# BTL_IOT_STM32.net
KiCad netlist of a schematic drawn in Altium Designer
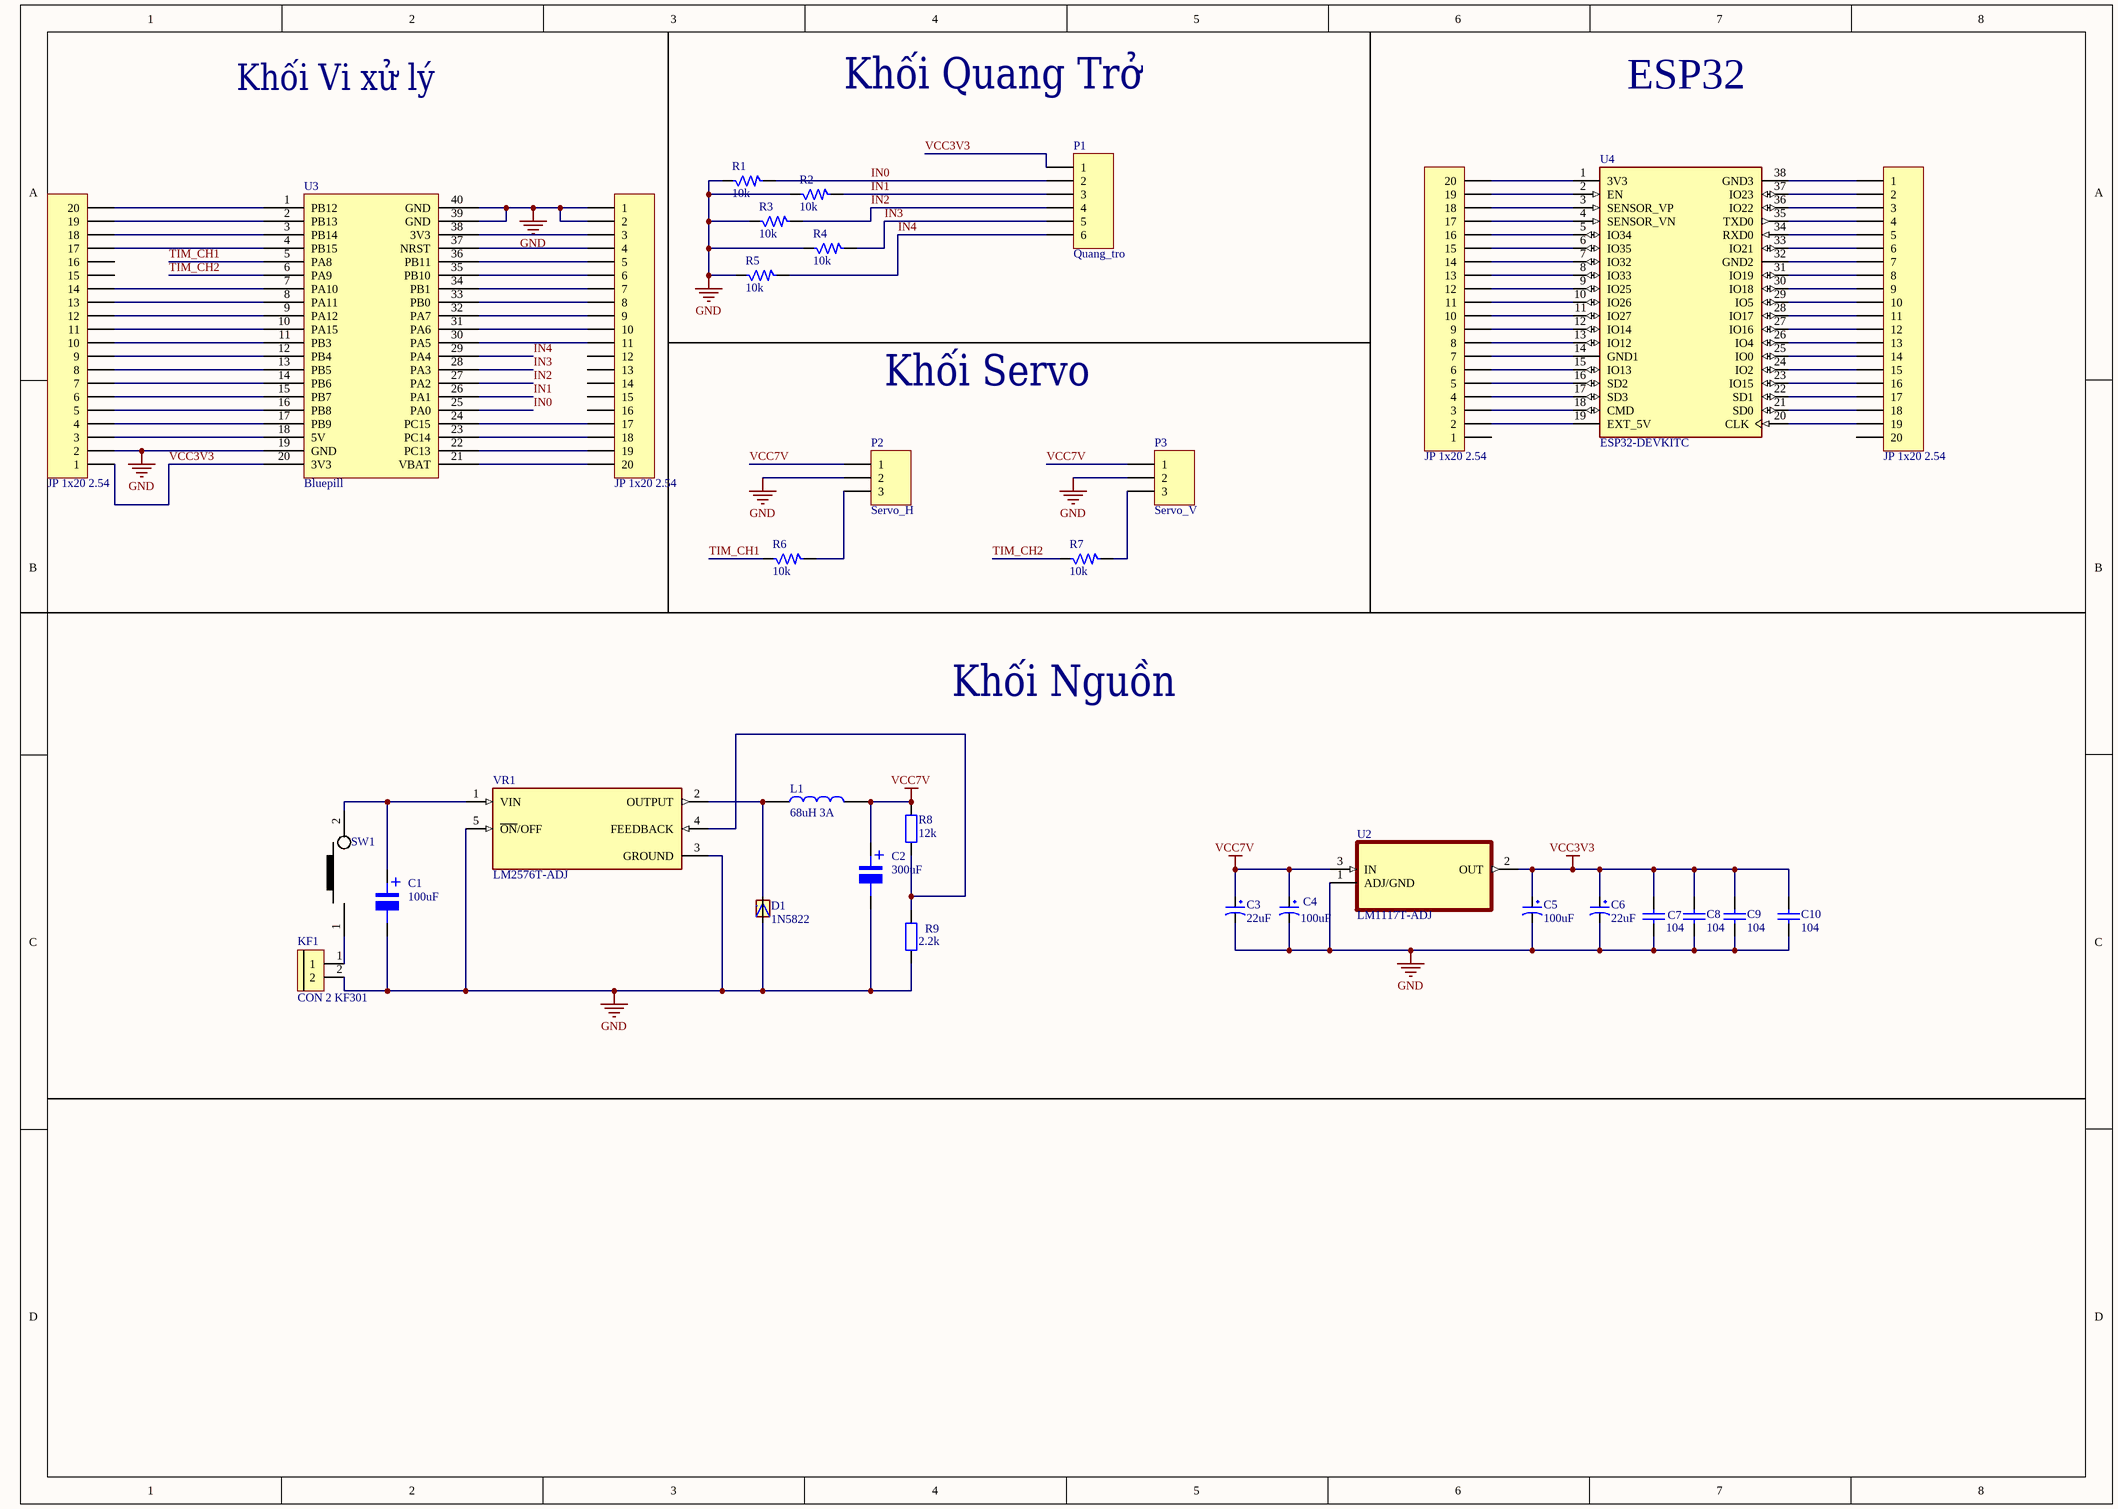
[diagram p0: BTL_IOT_STM32.SchDoc]

(export (version "E")
  (design (tool "Eeschema 10.0.6"))
  (components
    (comp (ref "C1")
      (value "100uF")
      (footprint "CA-ALU-5R")
      (description "Dán")
      (libsource (lib "Tu dien") (part "Tu Nhom 100uF 16V"))
    )
    (comp (ref "C2")
      (value "300uF")
      (footprint "CA-ALU-5R")
      (description "Dán")
      (libsource (lib "Tu dien") (part "Tu Nhom 100uF 16V"))
    )
    (comp (ref "C3")
      (value "22uF")
      (footprint "CA-ALU-5R")
      (description "Dán")
      (libsource (lib "Tu dien") (part "Tu tantalum 22uF 25V SMD6032"))
    )
    (comp (ref "C4")
      (value "100uF")
      (footprint "CA-ALU-5R")
      (description "Dán")
      (libsource (lib "Tu dien") (part "Tu tantalum 100uF 10V SMD6032"))
    )
    (comp (ref "C5")
      (value "100uF")
      (footprint "CA-ALU-5R")
      (description "Dán")
      (libsource (lib "Tu dien") (part "Tu tantalum 100uF 10V SMD6032"))
    )
    (comp (ref "C6")
      (value "22uF")
      (footprint "CA-ALU-5R")
      (description "Dán")
      (libsource (lib "Tu dien") (part "Tu tantalum 22uF 25V SMD6032"))
    )
    (comp (ref "C7")
      (value "104")
      (footprint "CN1")
      (description "Dán")
      (libsource (lib "Tu dien") (part "Tu 0603 104 50V 10%"))
    )
    (comp (ref "C8")
      (value "104")
      (footprint "CN1")
      (description "Dán")
      (libsource (lib "Tu dien") (part "Tu 0603 104 50V 10%"))
    )
    (comp (ref "C9")
      (value "104")
      (footprint "CN1")
      (description "Dán")
      (libsource (lib "Tu dien") (part "Tu 0603 104 50V 10%"))
    )
    (comp (ref "C10")
      (value "104")
      (footprint "CN1")
      (description "Dán")
      (libsource (lib "Tu dien") (part "Tu 0603 104 50V 10%"))
    )
    (comp (ref "D1")
      (value "1N5822")
      (footprint "DIOAD2120W130L950D530P")
      (description "Diode Schottky 40 V 3A Through Hole DO-201AD")
      (fields (field (name "MF") "STMicroelectronics"))
      (libsource (lib "1N5822") (part "1N5822"))
    )
    (comp (ref "JP1")
      (value "JP 1x20 2.54")
      (footprint "JP 1x20 CC")
      (description "Cắm")
      (libsource (lib "Jump") (part "JP 1x20 2.54 Cai Cong"))
    )
    (comp (ref "JP2")
      (value "JP 1x20 2.54")
      (footprint "JP 1x20 CC")
      (description "Cắm")
      (libsource (lib "") (part "JP 1x20 2.54 Cai Cong_1"))
    )
    (comp (ref "JP3")
      (value "JP 1x20 2.54")
      (footprint "JP 1x20 CC")
      (description "Cắm")
      (libsource (lib "Jump") (part "JP 1x20 2.54 Cai Cong"))
    )
    (comp (ref "JP4")
      (value "JP 1x20 2.54")
      (footprint "JP 1x20 CC")
      (description "Cắm")
      (libsource (lib "") (part "JP 1x20 2.54 Cai Cong_1"))
    )
    (comp (ref "KF1")
      (value "CON 2 KF301")
      (footprint "Con 2 KF301 5.08")
      (description "Cắm")
      (libsource (lib "Connector") (part "CON 2 KF301"))
    )
    (comp (ref "L1")
      (value "68uH 3A")
      (footprint "CUON CAM 100uH3A")
      (description "Dán")
      (libsource (lib "Cuon Cam") (part "CUON CAM 100uH DIP"))
    )
    (comp (ref "P1")
      (value "Quang_tro")
      (footprint "HDR1X6")
      (description "Header, 6-Pin")
      (fields (field (name "PUBLISHER") "Altium Limited"))
      (libsource (lib "Library AL") (part "Header 6"))
    )
    (comp (ref "P2")
      (value "Servo_H")
      (footprint "HDR1X3")
      (description "Header, 3-Pin")
      (fields (field (name "PUBLISHER") "Altium Limited"))
      (libsource (lib "Library AL") (part "Header 3"))
    )
    (comp (ref "P3")
      (value "Servo_V")
      (footprint "HDR1X3")
      (description "Header, 3-Pin")
      (fields (field (name "PUBLISHER") "Altium Limited"))
      (libsource (lib "Library AL") (part "Header 3"))
    )
    (comp (ref "R1")
      (value "10k")
      (footprint "R1/8W")
      (description "Resistor 1/4W")
      (libsource (lib "My Library") (part "R"))
    )
    (comp (ref "R2")
      (value "10k")
      (footprint "R1/8W")
      (description "Resistor 1/4W")
      (libsource (lib "My Library") (part "R"))
    )
    (comp (ref "R3")
      (value "10k")
      (footprint "R1/8W")
      (description "Resistor 1/4W")
      (libsource (lib "My Library") (part "R"))
    )
    (comp (ref "R4")
      (value "10k")
      (footprint "R1/8W")
      (description "Resistor 1/4W")
      (libsource (lib "My Library") (part "R"))
    )
    (comp (ref "R5")
      (value "10k")
      (footprint "R1/8W")
      (description "Resistor 1/4W")
      (libsource (lib "My Library") (part "R"))
    )
    (comp (ref "R6")
      (value "10k")
      (footprint "R1/8W")
      (description "Resistor 1/4W")
      (libsource (lib "My Library") (part "R"))
    )
    (comp (ref "R7")
      (value "10k")
      (footprint "R1/8W")
      (description "Resistor 1/4W")
      (libsource (lib "My Library") (part "R"))
    )
    (comp (ref "R8")
      (value "12k")
      (footprint "tro vach 1/4w")
      (description "Cắm")
      (libsource (lib "Dien Tro") (part "Tro Vach 1/4W 5% 12k"))
    )
    (comp (ref "R9")
      (value "2.2k")
      (footprint "tro vach 1/4w")
      (description "Cắm")
      (libsource (lib "Dien Tro") (part "Tro Vach 1/4W 5% 2.2k"))
    )
    (comp (ref "SW1")
      (value "SWITCH 10A-2PIN")
      (footprint "SW_2ARS_TH")
      (description "Rocker Switch SPST 16A (AC), 10A (DC) 250V Panel Mount, Snap-In")
      (fields
        (field (name "MANUFACTURER") "Würth Elektronik")
        (field (name "MANUFACTURER PART NUMBER") "471005264153")
      )
      (libsource (lib "Component") (part "SW1_RS-471005264153-TH"))
    )
    (comp (ref "U2")
      (value "LM1117T-ADJ")
      (footprint "TO254P470X1016X2222-3P")
      (description "Linear Voltage Regulator IC 1 Output 800mA TO-220-3")
      (fields (field (name "MP") "LM1117TADJ") (field (name "MF") "Texas Instruments"))
      (libsource (lib "LM1117T-ADJ") (part "LM1117T-ADJ"))
    )
    (comp (ref "U3")
      (value "Bluepill")
      (footprint "Blue Pill")
      (description "STM32F103C8T6")
      (libsource (lib "Bluepill") (part "STM32F103C8T6"))
    )
    (comp (ref "U4")
      (value "ESP32-DEVKITC")
      (footprint "MODULE_ESP32-DEVKITC")
      (fields (field (name "MF") "Espressif Systems"))
      (libsource (lib "ESP32-DEVKITC") (part "ESP32-DEVKITC"))
    )
    (comp (ref "VR1")
      (value "LM2576T-ADJ")
      (footprint "TO170P1067X483X1651-5")
      (description "SIMPLE SWITCHER&reg; 40V, 3A Low Component Count Step-Down Regulator 5-TO-220 -40 to 125")
      (fields (field (name "MF") "Texas Instruments"))
      (libsource (lib "LM2576T-ADJ") (part "LM2576T-ADJ"))
    )
  )
  (nets
    (net (code "1") (name "/IN0") (class "Default")
      (node (ref "P1") (pin "2") (pinfunction "2_2") (pintype "passive"))
      (node (ref "R1") (pin "2") (pinfunction "2_2") (pintype "passive"))
      (node (ref "U3") (pin "25") (pinfunction "PA0_25") (pintype "passive"))
    )
    (net (code "2") (name "/IN1") (class "Default")
      (node (ref "P1") (pin "3") (pinfunction "3_3") (pintype "passive"))
      (node (ref "R2") (pin "2") (pinfunction "2_2") (pintype "passive"))
      (node (ref "U3") (pin "26") (pinfunction "PA1_26") (pintype "passive"))
    )
    (net (code "3") (name "/IN2") (class "Default")
      (node (ref "P1") (pin "4") (pinfunction "4_4") (pintype "passive"))
      (node (ref "R3") (pin "2") (pinfunction "2_2") (pintype "passive"))
      (node (ref "U3") (pin "27") (pinfunction "PA2_27") (pintype "passive"))
    )
    (net (code "4") (name "/IN3") (class "Default")
      (node (ref "P1") (pin "5") (pinfunction "5_5") (pintype "passive"))
      (node (ref "R4") (pin "2") (pinfunction "2_2") (pintype "passive"))
      (node (ref "U3") (pin "28") (pinfunction "PA3_28") (pintype "passive"))
    )
    (net (code "5") (name "/IN4") (class "Default")
      (node (ref "P1") (pin "6") (pinfunction "6_6") (pintype "passive"))
      (node (ref "R5") (pin "2") (pinfunction "2_2") (pintype "passive"))
      (node (ref "U3") (pin "29") (pinfunction "PA4_29") (pintype "passive"))
    )
    (net (code "6") (name "/TIM_CH1") (class "Default")
      (node (ref "R6") (pin "1") (pinfunction "1_1") (pintype "passive"))
      (node (ref "U3") (pin "5") (pinfunction "PA8_5") (pintype "passive"))
    )
    (net (code "7") (name "/TIM_CH2") (class "Default")
      (node (ref "R7") (pin "1") (pinfunction "1_1") (pintype "passive"))
      (node (ref "U3") (pin "6") (pinfunction "PA9_6") (pintype "passive"))
    )
    (net (code "8") (name "GND") (class "Default")
      (node (ref "C1") (pin "2") (pinfunction "2_2") (pintype "passive"))
      (node (ref "C10") (pin "2") (pinfunction "2_2") (pintype "passive"))
      (node (ref "C2") (pin "2") (pinfunction "2_2") (pintype "passive"))
      (node (ref "C3") (pin "2") (pinfunction "2_2") (pintype "passive"))
      (node (ref "C4") (pin "2") (pinfunction "2_2") (pintype "passive"))
      (node (ref "C5") (pin "2") (pinfunction "2_2") (pintype "passive"))
      (node (ref "C6") (pin "2") (pinfunction "2_2") (pintype "passive"))
      (node (ref "C7") (pin "2") (pinfunction "2_2") (pintype "passive"))
      (node (ref "C8") (pin "2") (pinfunction "2_2") (pintype "passive"))
      (node (ref "C9") (pin "2") (pinfunction "2_2") (pintype "passive"))
      (node (ref "D1") (pin "A") (pinfunction "A_A") (pintype "passive"))
      (node (ref "JP3") (pin "2") (pinfunction "2_2") (pintype "passive"))
      (node (ref "JP4") (pin "1") (pinfunction "1_1") (pintype "passive"))
      (node (ref "JP4") (pin "2") (pinfunction "2_2") (pintype "passive"))
      (node (ref "KF1") (pin "2") (pinfunction "2_2") (pintype "passive"))
      (node (ref "P2") (pin "2") (pinfunction "2_2") (pintype "passive"))
      (node (ref "P3") (pin "2") (pinfunction "2_2") (pintype "passive"))
      (node (ref "R1") (pin "1") (pinfunction "1_1") (pintype "passive"))
      (node (ref "R2") (pin "1") (pinfunction "1_1") (pintype "passive"))
      (node (ref "R3") (pin "1") (pinfunction "1_1") (pintype "passive"))
      (node (ref "R4") (pin "1") (pinfunction "1_1") (pintype "passive"))
      (node (ref "R5") (pin "1") (pinfunction "1_1") (pintype "passive"))
      (node (ref "R9") (pin "1") (pinfunction "1_1") (pintype "passive"))
      (node (ref "U2") (pin "1") (pinfunction "ADJ/GND_1") (pintype "passive"))
      (node (ref "U3") (pin "19") (pinfunction "GND_19") (pintype "passive"))
      (node (ref "U3") (pin "39") (pinfunction "GND_39") (pintype "passive"))
      (node (ref "U3") (pin "40") (pinfunction "GND_40") (pintype "passive"))
      (node (ref "VR1") (pin "3") (pinfunction "GROUND_3") (pintype "power_in"))
      (node (ref "VR1") (pin "5") (pinfunction "~{ON}/OFF_5") (pintype "input"))
    )
    (net (code "9") (name "Net-(JP4-Pad3)") (class "Default")
      (node (ref "JP4") (pin "3") (pinfunction "3_3") (pintype "passive"))
      (node (ref "U3") (pin "38") (pinfunction "3V3_38") (pintype "passive"))
    )
    (net (code "10") (name "Net-(KF1-Pad1)") (class "Default")
      (node (ref "KF1") (pin "1") (pinfunction "1_1") (pintype "passive"))
      (node (ref "SW1") (pin "1") (pinfunction "1_1") (pintype "passive"))
    )
    (net (code "11") (name "Net-(P2-Pad3)") (class "Default")
      (node (ref "P2") (pin "3") (pinfunction "3_3") (pintype "passive"))
      (node (ref "R6") (pin "2") (pinfunction "2_2") (pintype "passive"))
    )
    (net (code "12") (name "Net-(P3-Pad3)") (class "Default")
      (node (ref "P3") (pin "3") (pinfunction "3_3") (pintype "passive"))
      (node (ref "R7") (pin "2") (pinfunction "2_2") (pintype "passive"))
    )
    (net (code "13") (name "Net-(U3-5V)") (class "Default")
      (node (ref "JP3") (pin "3") (pinfunction "3_3") (pintype "passive"))
      (node (ref "U3") (pin "18") (pinfunction "5V_18") (pintype "passive"))
    )
    (net (code "14") (name "Net-(U3-NRST)") (class "Default")
      (node (ref "JP4") (pin "4") (pinfunction "4_4") (pintype "passive"))
      (node (ref "U3") (pin "37") (pinfunction "NRST_37") (pintype "passive"))
    )
    (net (code "15") (name "Net-(U3-PA5)") (class "Default")
      (node (ref "JP4") (pin "11") (pinfunction "11_11") (pintype "passive"))
      (node (ref "U3") (pin "30") (pinfunction "PA5_30") (pintype "passive"))
    )
    (net (code "16") (name "Net-(U3-PA6)") (class "Default")
      (node (ref "JP4") (pin "10") (pinfunction "10_10") (pintype "passive"))
      (node (ref "U3") (pin "31") (pinfunction "PA6_31") (pintype "passive"))
    )
    (net (code "17") (name "Net-(U3-PA7)") (class "Default")
      (node (ref "JP4") (pin "9") (pinfunction "9_9") (pintype "passive"))
      (node (ref "U3") (pin "32") (pinfunction "PA7_32") (pintype "passive"))
    )
    (net (code "18") (name "Net-(U3-PA10)") (class "Default")
      (node (ref "JP3") (pin "14") (pinfunction "14_14") (pintype "passive"))
      (node (ref "U3") (pin "7") (pinfunction "PA10_7") (pintype "passive"))
    )
    (net (code "19") (name "Net-(U3-PA11)") (class "Default")
      (node (ref "JP3") (pin "13") (pinfunction "13_13") (pintype "passive"))
      (node (ref "U3") (pin "8") (pinfunction "PA11_8") (pintype "passive"))
    )
    (net (code "20") (name "Net-(U3-PA12)") (class "Default")
      (node (ref "JP3") (pin "12") (pinfunction "12_12") (pintype "passive"))
      (node (ref "U3") (pin "9") (pinfunction "PA12_9") (pintype "passive"))
    )
    (net (code "21") (name "Net-(U3-PA15)") (class "Default")
      (node (ref "JP3") (pin "11") (pinfunction "11_11") (pintype "passive"))
      (node (ref "U3") (pin "10") (pinfunction "PA15_10") (pintype "passive"))
    )
    (net (code "22") (name "Net-(U3-PB0)") (class "Default")
      (node (ref "JP4") (pin "8") (pinfunction "8_8") (pintype "passive"))
      (node (ref "U3") (pin "33") (pinfunction "PB0_33") (pintype "passive"))
    )
    (net (code "23") (name "Net-(U3-PB1)") (class "Default")
      (node (ref "JP4") (pin "7") (pinfunction "7_7") (pintype "passive"))
      (node (ref "U3") (pin "34") (pinfunction "PB1_34") (pintype "passive"))
    )
    (net (code "24") (name "Net-(U3-PB3)") (class "Default")
      (node (ref "JP3") (pin "10") (pinfunction "10_10") (pintype "passive"))
      (node (ref "U3") (pin "11") (pinfunction "PB3_11") (pintype "passive"))
    )
    (net (code "25") (name "Net-(U3-PB4)") (class "Default")
      (node (ref "JP3") (pin "9") (pinfunction "9_9") (pintype "passive"))
      (node (ref "U3") (pin "12") (pinfunction "PB4_12") (pintype "passive"))
    )
    (net (code "26") (name "Net-(U3-PB5)") (class "Default")
      (node (ref "JP3") (pin "8") (pinfunction "8_8") (pintype "passive"))
      (node (ref "U3") (pin "13") (pinfunction "PB5_13") (pintype "passive"))
    )
    (net (code "27") (name "Net-(U3-PB6)") (class "Default")
      (node (ref "JP3") (pin "7") (pinfunction "7_7") (pintype "passive"))
      (node (ref "U3") (pin "14") (pinfunction "PB6_14") (pintype "passive"))
    )
    (net (code "28") (name "Net-(U3-PB7)") (class "Default")
      (node (ref "JP3") (pin "6") (pinfunction "6_6") (pintype "passive"))
      (node (ref "U3") (pin "15") (pinfunction "PB7_15") (pintype "passive"))
    )
    (net (code "29") (name "Net-(U3-PB8)") (class "Default")
      (node (ref "JP3") (pin "5") (pinfunction "5_5") (pintype "passive"))
      (node (ref "U3") (pin "16") (pinfunction "PB8_16") (pintype "passive"))
    )
    (net (code "30") (name "Net-(U3-PB9)") (class "Default")
      (node (ref "JP3") (pin "4") (pinfunction "4_4") (pintype "passive"))
      (node (ref "U3") (pin "17") (pinfunction "PB9_17") (pintype "passive"))
    )
    (net (code "31") (name "Net-(U3-PB10)") (class "Default")
      (node (ref "JP4") (pin "6") (pinfunction "6_6") (pintype "passive"))
      (node (ref "U3") (pin "35") (pinfunction "PB10_35") (pintype "passive"))
    )
    (net (code "32") (name "Net-(U3-PB11)") (class "Default")
      (node (ref "JP4") (pin "5") (pinfunction "5_5") (pintype "passive"))
      (node (ref "U3") (pin "36") (pinfunction "PB11_36") (pintype "passive"))
    )
    (net (code "33") (name "Net-(U3-PB12)") (class "Default")
      (node (ref "JP3") (pin "20") (pinfunction "20_20") (pintype "passive"))
      (node (ref "U3") (pin "1") (pinfunction "PB12_1") (pintype "passive"))
    )
    (net (code "34") (name "Net-(U3-PB13)") (class "Default")
      (node (ref "JP3") (pin "19") (pinfunction "19_19") (pintype "passive"))
      (node (ref "U3") (pin "2") (pinfunction "PB13_2") (pintype "passive"))
    )
    (net (code "35") (name "Net-(U3-PB14)") (class "Default")
      (node (ref "JP3") (pin "18") (pinfunction "18_18") (pintype "passive"))
      (node (ref "U3") (pin "3") (pinfunction "PB14_3") (pintype "passive"))
    )
    (net (code "36") (name "Net-(U3-PB15)") (class "Default")
      (node (ref "JP3") (pin "17") (pinfunction "17_17") (pintype "passive"))
      (node (ref "U3") (pin "4") (pinfunction "PB15_4") (pintype "passive"))
    )
    (net (code "37") (name "Net-(U3-PC13)") (class "Default")
      (node (ref "JP4") (pin "19") (pinfunction "19_19") (pintype "passive"))
      (node (ref "U3") (pin "22") (pinfunction "PC13_22") (pintype "passive"))
    )
    (net (code "38") (name "Net-(U3-PC14)") (class "Default")
      (node (ref "JP4") (pin "18") (pinfunction "18_18") (pintype "passive"))
      (node (ref "U3") (pin "23") (pinfunction "PC14_23") (pintype "passive"))
    )
    (net (code "39") (name "Net-(U3-PC15)") (class "Default")
      (node (ref "JP4") (pin "17") (pinfunction "17_17") (pintype "passive"))
      (node (ref "U3") (pin "24") (pinfunction "PC15_24") (pintype "passive"))
    )
    (net (code "40") (name "Net-(U3-VBAT)") (class "Default")
      (node (ref "JP4") (pin "20") (pinfunction "20_20") (pintype "passive"))
      (node (ref "U3") (pin "21") (pinfunction "VBAT_21") (pintype "passive"))
    )
    (net (code "41") (name "Net-(U4-3V3)") (class "Default")
      (node (ref "JP1") (pin "20") (pinfunction "20_20") (pintype "passive"))
      (node (ref "U4") (pin "1") (pinfunction "3V3_1") (pintype "power_in"))
    )
    (net (code "42") (name "Net-(U4-CLK)") (class "Default")
      (node (ref "JP2") (pin "19") (pinfunction "19_19") (pintype "passive"))
      (node (ref "U4") (pin "20") (pinfunction "CLK_20") (pintype "input"))
    )
    (net (code "43") (name "Net-(U4-CMD)") (class "Default")
      (node (ref "JP1") (pin "3") (pinfunction "3_3") (pintype "passive"))
      (node (ref "U4") (pin "18") (pinfunction "CMD_18") (pintype "bidirectional"))
    )
    (net (code "44") (name "Net-(U4-EN)") (class "Default")
      (node (ref "JP1") (pin "19") (pinfunction "19_19") (pintype "passive"))
      (node (ref "U4") (pin "2") (pinfunction "EN_2") (pintype "input"))
    )
    (net (code "45") (name "Net-(U4-EXT_5V)") (class "Default")
      (node (ref "JP1") (pin "2") (pinfunction "2_2") (pintype "passive"))
      (node (ref "U4") (pin "19") (pinfunction "EXT_5V_19") (pintype "power_in"))
    )
    (net (code "46") (name "Net-(U4-GND1)") (class "Default")
      (node (ref "JP1") (pin "7") (pinfunction "7_7") (pintype "passive"))
      (node (ref "U4") (pin "14") (pinfunction "GND1_14") (pintype "power_in"))
    )
    (net (code "47") (name "Net-(U4-GND2)") (class "Default")
      (node (ref "JP2") (pin "7") (pinfunction "7_7") (pintype "passive"))
      (node (ref "U4") (pin "32") (pinfunction "GND2_32") (pintype "power_in"))
    )
    (net (code "48") (name "Net-(U4-GND3)") (class "Default")
      (node (ref "JP2") (pin "1") (pinfunction "1_1") (pintype "passive"))
      (node (ref "U4") (pin "38") (pinfunction "GND3_38") (pintype "power_in"))
    )
    (net (code "49") (name "Net-(U4-IO0)") (class "Default")
      (node (ref "JP2") (pin "14") (pinfunction "14_14") (pintype "passive"))
      (node (ref "U4") (pin "25") (pinfunction "IO0_25") (pintype "bidirectional"))
    )
    (net (code "50") (name "Net-(U4-IO2)") (class "Default")
      (node (ref "JP2") (pin "15") (pinfunction "15_15") (pintype "passive"))
      (node (ref "U4") (pin "24") (pinfunction "IO2_24") (pintype "bidirectional"))
    )
    (net (code "51") (name "Net-(U4-IO4)") (class "Default")
      (node (ref "JP2") (pin "13") (pinfunction "13_13") (pintype "passive"))
      (node (ref "U4") (pin "26") (pinfunction "IO4_26") (pintype "bidirectional"))
    )
    (net (code "52") (name "Net-(U4-IO5)") (class "Default")
      (node (ref "JP2") (pin "10") (pinfunction "10_10") (pintype "passive"))
      (node (ref "U4") (pin "29") (pinfunction "IO5_29") (pintype "bidirectional"))
    )
    (net (code "53") (name "Net-(U4-IO12)") (class "Default")
      (node (ref "JP1") (pin "8") (pinfunction "8_8") (pintype "passive"))
      (node (ref "U4") (pin "13") (pinfunction "IO12_13") (pintype "bidirectional"))
    )
    (net (code "54") (name "Net-(U4-IO13)") (class "Default")
      (node (ref "JP1") (pin "6") (pinfunction "6_6") (pintype "passive"))
      (node (ref "U4") (pin "15") (pinfunction "IO13_15") (pintype "bidirectional"))
    )
    (net (code "55") (name "Net-(U4-IO14)") (class "Default")
      (node (ref "JP1") (pin "9") (pinfunction "9_9") (pintype "passive"))
      (node (ref "U4") (pin "12") (pinfunction "IO14_12") (pintype "bidirectional"))
    )
    (net (code "56") (name "Net-(U4-IO15)") (class "Default")
      (node (ref "JP2") (pin "16") (pinfunction "16_16") (pintype "passive"))
      (node (ref "U4") (pin "23") (pinfunction "IO15_23") (pintype "bidirectional"))
    )
    (net (code "57") (name "Net-(U4-IO16)") (class "Default")
      (node (ref "JP2") (pin "12") (pinfunction "12_12") (pintype "passive"))
      (node (ref "U4") (pin "27") (pinfunction "IO16_27") (pintype "bidirectional"))
    )
    (net (code "58") (name "Net-(U4-IO17)") (class "Default")
      (node (ref "JP2") (pin "11") (pinfunction "11_11") (pintype "passive"))
      (node (ref "U4") (pin "28") (pinfunction "IO17_28") (pintype "bidirectional"))
    )
    (net (code "59") (name "Net-(U4-IO18)") (class "Default")
      (node (ref "JP2") (pin "9") (pinfunction "9_9") (pintype "passive"))
      (node (ref "U4") (pin "30") (pinfunction "IO18_30") (pintype "bidirectional"))
    )
    (net (code "60") (name "Net-(U4-IO19)") (class "Default")
      (node (ref "JP2") (pin "8") (pinfunction "8_8") (pintype "passive"))
      (node (ref "U4") (pin "31") (pinfunction "IO19_31") (pintype "bidirectional"))
    )
    (net (code "61") (name "Net-(U4-IO21)") (class "Default")
      (node (ref "JP2") (pin "6") (pinfunction "6_6") (pintype "passive"))
      (node (ref "U4") (pin "33") (pinfunction "IO21_33") (pintype "bidirectional"))
    )
    (net (code "62") (name "Net-(U4-IO22)") (class "Default")
      (node (ref "JP2") (pin "3") (pinfunction "3_3") (pintype "passive"))
      (node (ref "U4") (pin "36") (pinfunction "IO22_36") (pintype "bidirectional"))
    )
    (net (code "63") (name "Net-(U4-IO23)") (class "Default")
      (node (ref "JP2") (pin "2") (pinfunction "2_2") (pintype "passive"))
      (node (ref "U4") (pin "37") (pinfunction "IO23_37") (pintype "bidirectional"))
    )
    (net (code "64") (name "Net-(U4-IO25)") (class "Default")
      (node (ref "JP1") (pin "12") (pinfunction "12_12") (pintype "passive"))
      (node (ref "U4") (pin "9") (pinfunction "IO25_9") (pintype "bidirectional"))
    )
    (net (code "65") (name "Net-(U4-IO26)") (class "Default")
      (node (ref "JP1") (pin "11") (pinfunction "11_11") (pintype "passive"))
      (node (ref "U4") (pin "10") (pinfunction "IO26_10") (pintype "bidirectional"))
    )
    (net (code "66") (name "Net-(U4-IO27)") (class "Default")
      (node (ref "JP1") (pin "10") (pinfunction "10_10") (pintype "passive"))
      (node (ref "U4") (pin "11") (pinfunction "IO27_11") (pintype "bidirectional"))
    )
    (net (code "67") (name "Net-(U4-IO32)") (class "Default")
      (node (ref "JP1") (pin "14") (pinfunction "14_14") (pintype "passive"))
      (node (ref "U4") (pin "7") (pinfunction "IO32_7") (pintype "bidirectional"))
    )
    (net (code "68") (name "Net-(U4-IO33)") (class "Default")
      (node (ref "JP1") (pin "13") (pinfunction "13_13") (pintype "passive"))
      (node (ref "U4") (pin "8") (pinfunction "IO33_8") (pintype "bidirectional"))
    )
    (net (code "69") (name "Net-(U4-IO34)") (class "Default")
      (node (ref "JP1") (pin "16") (pinfunction "16_16") (pintype "passive"))
      (node (ref "U4") (pin "5") (pinfunction "IO34_5") (pintype "bidirectional"))
    )
    (net (code "70") (name "Net-(U4-IO35)") (class "Default")
      (node (ref "JP1") (pin "15") (pinfunction "15_15") (pintype "passive"))
      (node (ref "U4") (pin "6") (pinfunction "IO35_6") (pintype "bidirectional"))
    )
    (net (code "71") (name "Net-(U4-RXD0)") (class "Default")
      (node (ref "JP2") (pin "5") (pinfunction "5_5") (pintype "passive"))
      (node (ref "U4") (pin "34") (pinfunction "RXD0_34") (pintype "input"))
    )
    (net (code "72") (name "Net-(U4-SD0)") (class "Default")
      (node (ref "JP2") (pin "18") (pinfunction "18_18") (pintype "passive"))
      (node (ref "U4") (pin "21") (pinfunction "SD0_21") (pintype "bidirectional"))
    )
    (net (code "73") (name "Net-(U4-SD1)") (class "Default")
      (node (ref "JP2") (pin "17") (pinfunction "17_17") (pintype "passive"))
      (node (ref "U4") (pin "22") (pinfunction "SD1_22") (pintype "bidirectional"))
    )
    (net (code "74") (name "Net-(U4-SD2)") (class "Default")
      (node (ref "JP1") (pin "5") (pinfunction "5_5") (pintype "passive"))
      (node (ref "U4") (pin "16") (pinfunction "SD2_16") (pintype "bidirectional"))
    )
    (net (code "75") (name "Net-(U4-SD3)") (class "Default")
      (node (ref "JP1") (pin "4") (pinfunction "4_4") (pintype "passive"))
      (node (ref "U4") (pin "17") (pinfunction "SD3_17") (pintype "bidirectional"))
    )
    (net (code "76") (name "Net-(U4-SENSOR_VN)") (class "Default")
      (node (ref "JP1") (pin "17") (pinfunction "17_17") (pintype "passive"))
      (node (ref "U4") (pin "4") (pinfunction "SENSOR_VN_4") (pintype "input"))
    )
    (net (code "77") (name "Net-(U4-SENSOR_VP)") (class "Default")
      (node (ref "JP1") (pin "18") (pinfunction "18_18") (pintype "passive"))
      (node (ref "U4") (pin "3") (pinfunction "SENSOR_VP_3") (pintype "input"))
    )
    (net (code "78") (name "Net-(U4-TXD0)") (class "Default")
      (node (ref "JP2") (pin "4") (pinfunction "4_4") (pintype "passive"))
      (node (ref "U4") (pin "35") (pinfunction "TXD0_35") (pintype "output"))
    )
    (net (code "79") (name "Net-(VR1-FEEDBACK)") (class "Default")
      (node (ref "R8") (pin "1") (pinfunction "1_1") (pintype "passive"))
      (node (ref "R9") (pin "2") (pinfunction "2_2") (pintype "passive"))
      (node (ref "VR1") (pin "4") (pinfunction "FEEDBACK_4") (pintype "input"))
    )
    (net (code "80") (name "Net-(VR1-OUTPUT)") (class "Default")
      (node (ref "D1") (pin "C") (pinfunction "C_C") (pintype "passive"))
      (node (ref "L1") (pin "1") (pinfunction "1_1") (pintype "passive"))
      (node (ref "VR1") (pin "2") (pinfunction "OUTPUT_2") (pintype "output"))
    )
    (net (code "81") (name "Net-(VR1-VIN)") (class "Default")
      (node (ref "C1") (pin "1") (pinfunction "1_1") (pintype "passive"))
      (node (ref "SW1") (pin "2") (pinfunction "2_2") (pintype "passive"))
      (node (ref "VR1") (pin "1") (pinfunction "VIN_1") (pintype "input"))
    )
    (net (code "82") (name "VCC3V3") (class "Default")
      (node (ref "C10") (pin "1") (pinfunction "1_1") (pintype "passive"))
      (node (ref "C5") (pin "1") (pinfunction "1_1") (pintype "passive"))
      (node (ref "C6") (pin "1") (pinfunction "1_1") (pintype "passive"))
      (node (ref "C7") (pin "1") (pinfunction "1_1") (pintype "passive"))
      (node (ref "C8") (pin "1") (pinfunction "1_1") (pintype "passive"))
      (node (ref "C9") (pin "1") (pinfunction "1_1") (pintype "passive"))
      (node (ref "JP3") (pin "1") (pinfunction "1_1") (pintype "passive"))
      (node (ref "P1") (pin "1") (pinfunction "1_1") (pintype "passive"))
      (node (ref "U2") (pin "2") (pinfunction "OUT_2") (pintype "output"))
      (node (ref "U3") (pin "20") (pinfunction "3V3_20") (pintype "passive"))
    )
    (net (code "83") (name "VCC7V") (class "Default")
      (node (ref "C2") (pin "1") (pinfunction "1_1") (pintype "passive"))
      (node (ref "C3") (pin "1") (pinfunction "1_1") (pintype "passive"))
      (node (ref "C4") (pin "1") (pinfunction "1_1") (pintype "passive"))
      (node (ref "L1") (pin "2") (pinfunction "2_2") (pintype "passive"))
      (node (ref "P2") (pin "1") (pinfunction "1_1") (pintype "passive"))
      (node (ref "P3") (pin "1") (pinfunction "1_1") (pintype "passive"))
      (node (ref "R8") (pin "2") (pinfunction "2_2") (pintype "passive"))
      (node (ref "U2") (pin "3") (pinfunction "IN_3") (pintype "input"))
    )
    (net (code "84") (name "unconnected-(JP1-Pad1)") (class "Default")
      (node (ref "JP1") (pin "1") (pinfunction "1_1") (pintype "passive"))
    )
    (net (code "85") (name "unconnected-(JP2-Pad20)") (class "Default")
      (node (ref "JP2") (pin "20") (pinfunction "20_20") (pintype "passive"))
    )
    (net (code "86") (name "unconnected-(JP3-Pad15)") (class "Default")
      (node (ref "JP3") (pin "15") (pinfunction "15_15") (pintype "passive"))
    )
    (net (code "87") (name "unconnected-(JP3-Pad16)") (class "Default")
      (node (ref "JP3") (pin "16") (pinfunction "16_16") (pintype "passive"))
    )
    (net (code "88") (name "unconnected-(JP4-Pad12)") (class "Default")
      (node (ref "JP4") (pin "12") (pinfunction "12_12") (pintype "passive"))
    )
    (net (code "89") (name "unconnected-(JP4-Pad13)") (class "Default")
      (node (ref "JP4") (pin "13") (pinfunction "13_13") (pintype "passive"))
    )
    (net (code "90") (name "unconnected-(JP4-Pad14)") (class "Default")
      (node (ref "JP4") (pin "14") (pinfunction "14_14") (pintype "passive"))
    )
    (net (code "91") (name "unconnected-(JP4-Pad15)") (class "Default")
      (node (ref "JP4") (pin "15") (pinfunction "15_15") (pintype "passive"))
    )
    (net (code "92") (name "unconnected-(JP4-Pad16)") (class "Default")
      (node (ref "JP4") (pin "16") (pinfunction "16_16") (pintype "passive"))
    )
  )
)
